# converter_v2.net
KiCad netlist of a schematic drawn in EAGLE
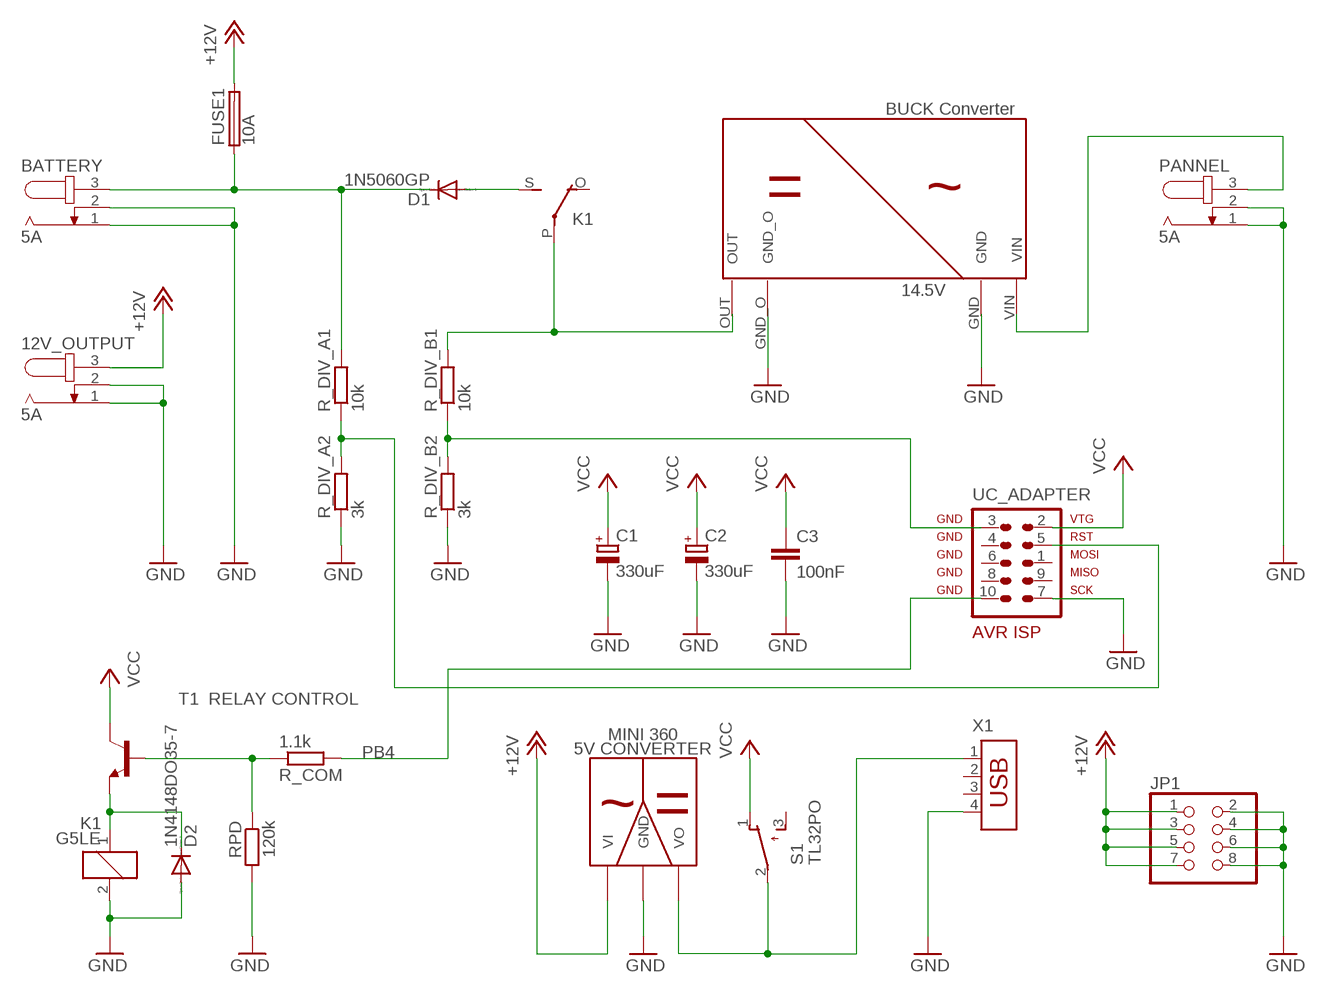
[diagram p0: schematic, sheet 1]

(export (version "E")
  (design (tool "Eeschema 10.0.6"))
  (components
    (comp (ref "12V_OUTPUT")
      (value "5A")
      (footprint "eagle-import:SPC4077")
      (libsource (lib "eagle-import") (part "JACK-PLUG0"))
    )
    (comp (ref "BATTERY")
      (value "5A")
      (footprint "eagle-import:SPC4077")
      (libsource (lib "eagle-import") (part "JACK-PLUG0"))
    )
    (comp (ref "C1")
      (value "330uF")
      (footprint "eagle-import:E2,5-7")
      (libsource (lib "eagle-import") (part "CPOL-EUE2.5-7"))
    )
    (comp (ref "C2")
      (value "330uF")
      (footprint "eagle-import:E2,5-7")
      (libsource (lib "eagle-import") (part "CPOL-EUE2.5-7"))
    )
    (comp (ref "C3")
      (value "100nF")
      (footprint "eagle-import:C025-030X050")
      (libsource (lib "eagle-import") (part "C-EU025-030X050"))
    )
    (comp (ref "D1")
      (value "1N5060GP")
      (footprint "eagle-import:DO15-12")
      (libsource (lib "eagle-import") (part "1N5060GP"))
    )
    (comp (ref "D2")
      (value "1N4148DO35-7")
      (footprint "eagle-import:DO35-7")
      (libsource (lib "eagle-import") (part "1N4148DO35-7"))
    )
    (comp (ref "FUSE1")
      (value "10A")
      (footprint "eagle-import:FUSE_HOLDER_5X20MM")
      (libsource (lib "eagle-import") (part "FUSEBLANK_5X20MM"))
    )
    (comp (ref "JP1")
      (value "PINHD-2X4")
      (footprint "eagle-import:2X04")
      (libsource (lib "eagle-import") (part "PINHD-2X4"))
    )
    (comp (ref "K1")
      (value "G5LE")
      (footprint "eagle-import:G5LE")
      (libsource (lib "eagle-import") (part "G5LE"))
    )
    (comp (ref "PANNEL")
      (value "5A")
      (footprint "eagle-import:SPC4077")
      (libsource (lib "eagle-import") (part "JACK-PLUG0"))
    )
    (comp (ref "RPD")
      (value "120k")
      (footprint "eagle-import:0207_10")
      (libsource (lib "eagle-import") (part "R-EU_0207/10"))
    )
    (comp (ref "R_COM")
      (value "1.1k")
      (footprint "eagle-import:0207_10")
      (libsource (lib "eagle-import") (part "R-EU_0207/10"))
    )
    (comp (ref "R_DIV_A1")
      (value "10k")
      (footprint "eagle-import:0207_10")
      (libsource (lib "eagle-import") (part "R-EU_0207/10"))
    )
    (comp (ref "R_DIV_A2")
      (value "3k")
      (footprint "eagle-import:0207_10")
      (libsource (lib "eagle-import") (part "R-EU_0207/10"))
    )
    (comp (ref "R_DIV_B1")
      (value "10k")
      (footprint "eagle-import:0207_10")
      (libsource (lib "eagle-import") (part "R-EU_0207/10"))
    )
    (comp (ref "R_DIV_B2")
      (value "3k")
      (footprint "eagle-import:0207_10")
      (libsource (lib "eagle-import") (part "R-EU_0207/10"))
    )
    (comp (ref "S1")
      (value "TL32PO")
      (footprint "eagle-import:TL3XPO")
      (libsource (lib "eagle-import") (part "TL32PO"))
    )
    (comp (ref "T1")
      (value "2N5551-NPN-TO92-EBC")
      (footprint "eagle-import:TO92-EBC")
      (libsource (lib "eagle-import") (part "-NPN-TO92-EBC2N5551"))
    )
    (comp (ref "U$1")
      (value "MINI_360MINI_360_PACK")
      (footprint "eagle-import:T-30")
      (libsource (lib "eagle-import") (part "MINI_360MINI_360_PACK"))
    )
    (comp (ref "U$2")
      (value "14.5V")
      (footprint "eagle-import:MINI360_IPX")
      (libsource (lib "eagle-import") (part "BUCK_CONVERTERBUCK"))
    )
    (comp (ref "UC_ADAPTER")
      (value "AVR-ISP-10")
      (footprint "eagle-import:AVR-ISP-10")
      (libsource (lib "eagle-import") (part "AVR-ISP-10"))
    )
    (comp (ref "X1")
      (value "USB-787616")
      (footprint "eagle-import:USB")
      (libsource (lib "eagle-import") (part "USB-787616"))
    )
  )
  (nets
    (net (code "1") (name "+12V") (class "Default")
      (node (ref "12V_OUTPUT") (pin "3") (pinfunction "3_3") (pintype "passive"))
      (node (ref "FUSE1") (pin "2") (pinfunction "2_2") (pintype "passive"))
      (node (ref "JP1") (pin "1") (pinfunction "1_1") (pintype "passive"))
      (node (ref "JP1") (pin "3") (pinfunction "3_3") (pintype "passive"))
      (node (ref "JP1") (pin "5") (pinfunction "5_5") (pintype "passive"))
      (node (ref "JP1") (pin "7") (pinfunction "7_7") (pintype "passive"))
      (node (ref "U$1") (pin "1") (pinfunction "VI_1") (pintype "bidirectional"))
    )
    (net (code "2") (name "/PB4") (class "Default")
      (node (ref "R_COM") (pin "2") (pinfunction "2_2") (pintype "passive"))
      (node (ref "UC_ADAPTER") (pin "10") (pinfunction "10_10") (pintype "passive"))
    )
    (net (code "3") (name "GND") (class "Default")
      (node (ref "12V_OUTPUT") (pin "1") (pinfunction "1_1") (pintype "passive"))
      (node (ref "12V_OUTPUT") (pin "2") (pinfunction "2_2") (pintype "passive"))
      (node (ref "BATTERY") (pin "1") (pinfunction "1_1") (pintype "passive"))
      (node (ref "BATTERY") (pin "2") (pinfunction "2_2") (pintype "passive"))
      (node (ref "C1") (pin "-") (pinfunction "-_-") (pintype "passive"))
      (node (ref "C2") (pin "-") (pinfunction "-_-") (pintype "passive"))
      (node (ref "C3") (pin "2") (pinfunction "2_2") (pintype "passive"))
      (node (ref "D2") (pin "A") (pinfunction "A_A") (pintype "passive"))
      (node (ref "JP1") (pin "2") (pinfunction "2_2") (pintype "passive"))
      (node (ref "JP1") (pin "4") (pinfunction "4_4") (pintype "passive"))
      (node (ref "JP1") (pin "6") (pinfunction "6_6") (pintype "passive"))
      (node (ref "JP1") (pin "8") (pinfunction "8_8") (pintype "passive"))
      (node (ref "K1") (pin "2") (pinfunction "2_2") (pintype "passive"))
      (node (ref "PANNEL") (pin "1") (pinfunction "1_1") (pintype "passive"))
      (node (ref "PANNEL") (pin "2") (pinfunction "2_2") (pintype "passive"))
      (node (ref "RPD") (pin "2") (pinfunction "2_2") (pintype "passive"))
      (node (ref "R_DIV_A2") (pin "1") (pinfunction "1_1") (pintype "passive"))
      (node (ref "R_DIV_B2") (pin "1") (pinfunction "1_1") (pintype "passive"))
      (node (ref "U$1") (pin "2") (pinfunction "GND_2") (pintype "bidirectional"))
      (node (ref "UC_ADAPTER") (pin "7") (pinfunction "7_7") (pintype "passive"))
      (node (ref "X1") (pin "4") (pinfunction "4_4") (pintype "passive"))
    )
    (net (code "4") (name "Net-(BATTERY-Pad3)") (class "Default")
      (node (ref "BATTERY") (pin "3") (pinfunction "3_3") (pintype "passive"))
      (node (ref "D1") (pin "C") (pinfunction "C_C") (pintype "passive"))
      (node (ref "FUSE1") (pin "1") (pinfunction "1_1") (pintype "passive"))
      (node (ref "R_DIV_A1") (pin "2") (pinfunction "2_2") (pintype "passive"))
    )
    (net (code "5") (name "Net-(D1-PadA)") (class "Default")
      (node (ref "D1") (pin "A") (pinfunction "A_A") (pintype "passive"))
      (node (ref "K1") (pin "S") (pinfunction "S_S") (pintype "passive"))
    )
    (net (code "6") (name "Net-(D2-PadC)") (class "Default")
      (node (ref "D2") (pin "C") (pinfunction "C_C") (pintype "passive"))
      (node (ref "K1") (pin "1") (pinfunction "1_1") (pintype "passive"))
      (node (ref "T1") (pin "E") (pinfunction "E_E") (pintype "passive"))
    )
    (net (code "7") (name "Net-(K1-PadP)") (class "Default")
      (node (ref "K1") (pin "P") (pinfunction "P_P") (pintype "passive"))
      (node (ref "R_DIV_B1") (pin "2") (pinfunction "2_2") (pintype "passive"))
    )
    (net (code "8") (name "Net-(PANNEL-Pad3)") (class "Default")
      (node (ref "PANNEL") (pin "3") (pinfunction "3_3") (pintype "passive"))
      (node (ref "U$2") (pin "VIN") (pinfunction "VIN_VIN") (pintype "bidirectional"))
    )
    (net (code "9") (name "Net-(RPD-Pad1)") (class "Default")
      (node (ref "RPD") (pin "1") (pinfunction "1_1") (pintype "passive"))
      (node (ref "R_COM") (pin "1") (pinfunction "1_1") (pintype "passive"))
      (node (ref "T1") (pin "B") (pinfunction "B_B") (pintype "passive"))
    )
    (net (code "10") (name "Net-(R_DIV_A1-Pad1)") (class "Default")
      (node (ref "R_DIV_A1") (pin "1") (pinfunction "1_1") (pintype "passive"))
      (node (ref "R_DIV_A2") (pin "2") (pinfunction "2_2") (pintype "passive"))
      (node (ref "UC_ADAPTER") (pin "5") (pinfunction "5_5") (pintype "passive"))
    )
    (net (code "11") (name "Net-(R_DIV_B1-Pad1)") (class "Default")
      (node (ref "R_DIV_B1") (pin "1") (pinfunction "1_1") (pintype "passive"))
      (node (ref "R_DIV_B2") (pin "2") (pinfunction "2_2") (pintype "passive"))
      (node (ref "UC_ADAPTER") (pin "3") (pinfunction "3_3") (pintype "passive"))
    )
    (net (code "12") (name "Net-(S1-P)") (class "Default")
      (node (ref "S1") (pin "2") (pinfunction "P_2") (pintype "passive"))
      (node (ref "U$1") (pin "3") (pinfunction "VO_3") (pintype "bidirectional"))
      (node (ref "X1") (pin "1") (pinfunction "1_1") (pintype "passive"))
    )
    (net (code "13") (name "VCC") (class "Default")
      (node (ref "C1") (pin "+") (pinfunction "+_+") (pintype "passive"))
      (node (ref "C2") (pin "+") (pinfunction "+_+") (pintype "passive"))
      (node (ref "C3") (pin "1") (pinfunction "1_1") (pintype "passive"))
      (node (ref "S1") (pin "1") (pinfunction "O_1") (pintype "passive"))
      (node (ref "T1") (pin "C") (pinfunction "C_C") (pintype "passive"))
      (node (ref "UC_ADAPTER") (pin "2") (pinfunction "2_2") (pintype "passive"))
    )
    (net (code "14") (name "unconnected-(K1-PadO)") (class "Default")
      (node (ref "K1") (pin "O") (pinfunction "O_O") (pintype "passive"))
    )
    (net (code "15") (name "unconnected-(S1-S-Pad3)") (class "Default")
      (node (ref "S1") (pin "3") (pinfunction "S_3") (pintype "passive"))
    )
    (net (code "16") (name "unconnected-(U$2-PadGND)") (class "Default")
      (node (ref "U$2") (pin "GND") (pinfunction "GND_GND") (pintype "bidirectional"))
    )
    (net (code "17") (name "unconnected-(U$2-PadGND_O)") (class "Default")
      (node (ref "U$2") (pin "GND_O") (pinfunction "GND_O_GND_O") (pintype "bidirectional"))
    )
    (net (code "18") (name "unconnected-(U$2-PadOUT)") (class "Default")
      (node (ref "U$2") (pin "OUT") (pinfunction "OUT_OUT") (pintype "bidirectional"))
    )
    (net (code "19") (name "unconnected-(UC_ADAPTER-Pad1)") (class "Default")
      (node (ref "UC_ADAPTER") (pin "1") (pinfunction "1_1") (pintype "passive"))
    )
    (net (code "20") (name "unconnected-(UC_ADAPTER-Pad4)") (class "Default")
      (node (ref "UC_ADAPTER") (pin "4") (pinfunction "4_4") (pintype "passive"))
    )
    (net (code "21") (name "unconnected-(UC_ADAPTER-Pad6)") (class "Default")
      (node (ref "UC_ADAPTER") (pin "6") (pinfunction "6_6") (pintype "passive"))
    )
    (net (code "22") (name "unconnected-(UC_ADAPTER-Pad8)") (class "Default")
      (node (ref "UC_ADAPTER") (pin "8") (pinfunction "8_8") (pintype "passive"))
    )
    (net (code "23") (name "unconnected-(UC_ADAPTER-Pad9)") (class "Default")
      (node (ref "UC_ADAPTER") (pin "9") (pinfunction "9_9") (pintype "passive"))
    )
    (net (code "24") (name "unconnected-(X1-Pad2)") (class "Default")
      (node (ref "X1") (pin "2") (pinfunction "2_2") (pintype "passive"))
    )
    (net (code "25") (name "unconnected-(X1-Pad3)") (class "Default")
      (node (ref "X1") (pin "3") (pinfunction "3_3") (pintype "passive"))
    )
  )
)
